# CPUCUIT.net
KiCad netlist of a schematic drawn in Altium Designer
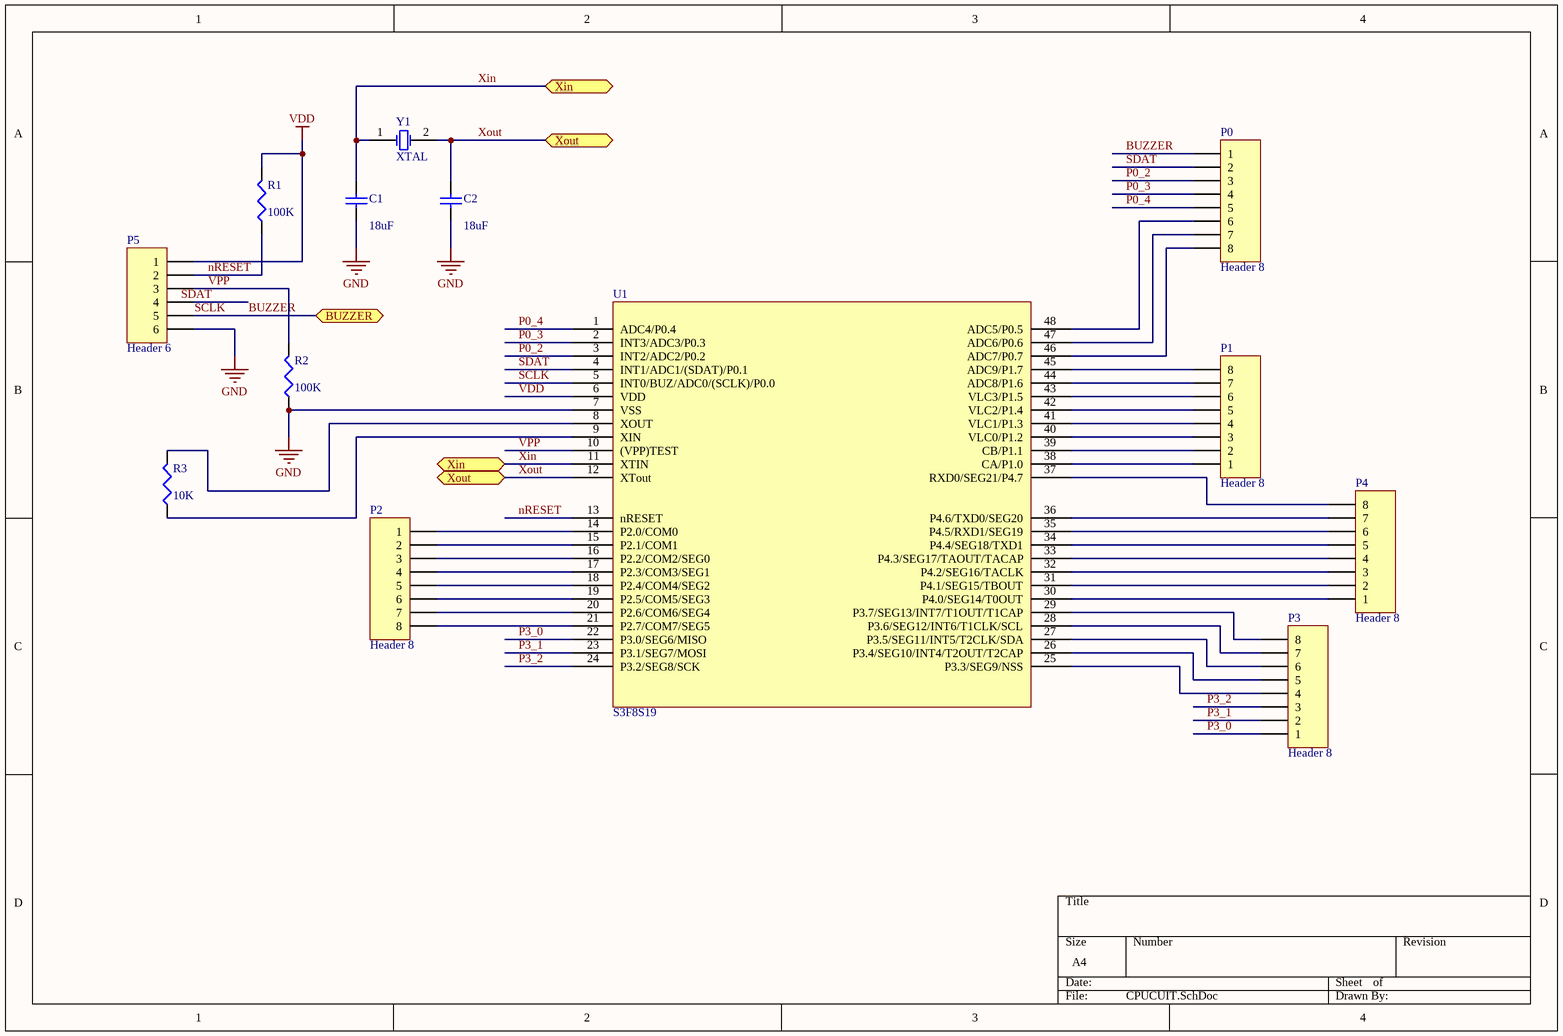
[diagram p0: CPUCUIT.SchDoc]

(export (version "E")
  (design (tool "Eeschema 10.0.6"))
  (components
    (comp (ref "C1")
      (value "18uF")
      (footprint "1608[0603]")
      (description "Capacitor (Semiconductor SIM Model)")
      (fields (field (name "Comment") "Cap Semi") (field (name "PUBLISHER") "Altium Limited"))
      (libsource (lib "Miscellaneous Devices") (part "Cap Semi"))
    )
    (comp (ref "C2")
      (value "18uF")
      (footprint "1608[0603]")
      (description "Capacitor (Semiconductor SIM Model)")
      (fields (field (name "Comment") "Cap Semi") (field (name "PUBLISHER") "Altium Limited"))
      (libsource (lib "Miscellaneous Devices") (part "Cap Semi"))
    )
    (comp (ref "P0")
      (value "Header 8")
      (footprint "HDR1X8")
      (description "Header, 8-Pin")
      (fields (field (name "PUBLISHER") "Altium Limited"))
      (libsource (lib "") (part "Header 8_1"))
    )
    (comp (ref "P1")
      (value "Header 8")
      (footprint "HDR1X8")
      (description "Header, 8-Pin")
      (fields (field (name "PUBLISHER") "Altium Limited"))
      (libsource (lib "Miscellaneous Connectors") (part "Header 8"))
    )
    (comp (ref "P2")
      (value "Header 8")
      (footprint "HDR1X8")
      (description "Header, 8-Pin")
      (fields (field (name "PUBLISHER") "Altium Limited"))
      (libsource (lib "") (part "Header 8_2"))
    )
    (comp (ref "P3")
      (value "Header 8")
      (footprint "HDR1X8")
      (description "Header, 8-Pin")
      (fields (field (name "PUBLISHER") "Altium Limited"))
      (libsource (lib "Miscellaneous Connectors") (part "Header 8"))
    )
    (comp (ref "P4")
      (value "Header 8")
      (footprint "HDR1X8")
      (description "Header, 8-Pin")
      (fields (field (name "PUBLISHER") "Altium Limited"))
      (libsource (lib "Miscellaneous Connectors") (part "Header 8"))
    )
    (comp (ref "P5")
      (value "Header 6")
      (footprint "HDR1X6")
      (description "Header, 6-Pin")
      (fields (field (name "PUBLISHER") "Altium Limited"))
      (libsource (lib "Miscellaneous Connectors") (part "Header 6"))
    )
    (comp (ref "R1")
      (value "100K")
      (footprint "J1-0603")
      (description "Resistor")
      (fields (field (name "Comment") "Res3") (field (name "PUBLISHER") "Altium Limited"))
      (libsource (lib "Miscellaneous Devices") (part "Res3"))
    )
    (comp (ref "R2")
      (value "100K")
      (footprint "J1-0603")
      (description "Resistor")
      (fields (field (name "Comment") "Res3") (field (name "PUBLISHER") "Altium Limited"))
      (libsource (lib "Miscellaneous Devices") (part "Res3"))
    )
    (comp (ref "R3")
      (value "10K")
      (footprint "J1-0603")
      (description "Resistor")
      (fields (field (name "Comment") "Res3") (field (name "PUBLISHER") "Altium Limited"))
      (libsource (lib "Miscellaneous Devices") (part "Res3"))
    )
    (comp (ref "U1")
      (value "S3F8S19")
      (footprint "QFP75P1335X1335X230-48N")
      (libsource (lib "IOTSchlib") (part "S3F8S19"))
    )
    (comp (ref "Y1")
      (value "XTAL")
      (footprint "R38")
      (description "Crystal Oscillator")
      (fields (field (name "PUBLISHER") "Altium Limited"))
      (libsource (lib "Miscellaneous Devices") (part "XTAL"))
    )
  )
  (nets
    (net (code "1") (name "/BUZZER") (class "Default")
      (node (ref "P0") (pin "1") (pinfunction "1_1") (pintype "passive"))
      (node (ref "P5") (pin "5") (pinfunction "5_5") (pintype "passive"))
      (node (ref "U1") (pin "5") (pinfunction "INT0/BUZ/ADC0/(SCLK)/P0.0_5") (pintype "passive"))
    )
    (net (code "2") (name "/P0_2") (class "Default")
      (node (ref "P0") (pin "3") (pinfunction "3_3") (pintype "passive"))
      (node (ref "U1") (pin "3") (pinfunction "INT2/ADC2/P0.2_3") (pintype "passive"))
    )
    (net (code "3") (name "/P0_3") (class "Default")
      (node (ref "P0") (pin "4") (pinfunction "4_4") (pintype "passive"))
      (node (ref "U1") (pin "2") (pinfunction "INT3/ADC3/P0.3_2") (pintype "passive"))
    )
    (net (code "4") (name "/P0_4") (class "Default")
      (node (ref "P0") (pin "5") (pinfunction "5_5") (pintype "passive"))
      (node (ref "U1") (pin "1") (pinfunction "ADC4/P0.4_1") (pintype "passive"))
    )
    (net (code "5") (name "/P3_0") (class "Default")
      (node (ref "P3") (pin "1") (pinfunction "1_1") (pintype "passive"))
      (node (ref "U1") (pin "22") (pinfunction "P3.0/SEG6/MISO_22") (pintype "passive"))
    )
    (net (code "6") (name "/P3_1") (class "Default")
      (node (ref "P3") (pin "2") (pinfunction "2_2") (pintype "passive"))
      (node (ref "U1") (pin "23") (pinfunction "P3.1/SEG7/MOSI_23") (pintype "passive"))
    )
    (net (code "7") (name "/P3_2") (class "Default")
      (node (ref "P3") (pin "3") (pinfunction "3_3") (pintype "passive"))
      (node (ref "U1") (pin "24") (pinfunction "P3.2/SEG8/SCK_24") (pintype "passive"))
    )
    (net (code "8") (name "/SDAT") (class "Default")
      (node (ref "P0") (pin "2") (pinfunction "2_2") (pintype "passive"))
      (node (ref "U1") (pin "4") (pinfunction "INT1/ADC1/(SDAT)/P0.1_4") (pintype "passive"))
    )
    (net (code "9") (name "/VPP") (class "Default")
      (node (ref "P5") (pin "3") (pinfunction "3_3") (pintype "passive"))
      (node (ref "R2") (pin "2") (pinfunction "2_2") (pintype "passive"))
      (node (ref "U1") (pin "10") (pinfunction "(VPP)TEST_10") (pintype "passive"))
    )
    (net (code "10") (name "/Xin") (class "Default")
      (node (ref "C1") (pin "2") (pinfunction "2_2") (pintype "passive"))
      (node (ref "U1") (pin "11") (pinfunction "XTIN_11") (pintype "passive"))
      (node (ref "Y1") (pin "1") (pinfunction "OSC1_1") (pintype "passive"))
    )
    (net (code "11") (name "/Xout") (class "Default")
      (node (ref "C2") (pin "2") (pinfunction "2_2") (pintype "passive"))
      (node (ref "U1") (pin "12") (pinfunction "XTout_12") (pintype "passive"))
      (node (ref "Y1") (pin "2") (pinfunction "OSC2_2") (pintype "passive"))
    )
    (net (code "12") (name "/nRESET") (class "Default")
      (node (ref "P5") (pin "2") (pinfunction "2_2") (pintype "passive"))
      (node (ref "R1") (pin "1") (pinfunction "1_1") (pintype "passive"))
      (node (ref "U1") (pin "13") (pinfunction "nRESET_13") (pintype "passive"))
    )
    (net (code "13") (name "GND") (class "Default")
      (node (ref "C1") (pin "1") (pinfunction "1_1") (pintype "passive"))
      (node (ref "C2") (pin "1") (pinfunction "1_1") (pintype "passive"))
      (node (ref "P5") (pin "6") (pinfunction "6_6") (pintype "passive"))
      (node (ref "R2") (pin "1") (pinfunction "1_1") (pintype "passive"))
      (node (ref "U1") (pin "7") (pinfunction "VSS_7") (pintype "passive"))
    )
    (net (code "14") (name "Net-(U1-ADC5{slash}P0.5)") (class "Default")
      (node (ref "P0") (pin "6") (pinfunction "6_6") (pintype "passive"))
      (node (ref "U1") (pin "48") (pinfunction "ADC5/P0.5_48") (pintype "passive"))
    )
    (net (code "15") (name "Net-(U1-ADC6{slash}P0.6)") (class "Default")
      (node (ref "P0") (pin "7") (pinfunction "7_7") (pintype "passive"))
      (node (ref "U1") (pin "47") (pinfunction "ADC6/P0.6_47") (pintype "passive"))
    )
    (net (code "16") (name "Net-(U1-ADC7{slash}P0.7)") (class "Default")
      (node (ref "P0") (pin "8") (pinfunction "8_8") (pintype "passive"))
      (node (ref "U1") (pin "46") (pinfunction "ADC7/P0.7_46") (pintype "passive"))
    )
    (net (code "17") (name "Net-(U1-ADC8{slash}P1.6)") (class "Default")
      (node (ref "P1") (pin "7") (pinfunction "7_7") (pintype "passive"))
      (node (ref "U1") (pin "44") (pinfunction "ADC8/P1.6_44") (pintype "passive"))
    )
    (net (code "18") (name "Net-(U1-ADC9{slash}P1.7)") (class "Default")
      (node (ref "P1") (pin "8") (pinfunction "8_8") (pintype "passive"))
      (node (ref "U1") (pin "45") (pinfunction "ADC9/P1.7_45") (pintype "passive"))
    )
    (net (code "19") (name "Net-(U1-CA{slash}P1.0)") (class "Default")
      (node (ref "P1") (pin "1") (pinfunction "1_1") (pintype "passive"))
      (node (ref "U1") (pin "38") (pinfunction "CA/P1.0_38") (pintype "passive"))
    )
    (net (code "20") (name "Net-(U1-CB{slash}P1.1)") (class "Default")
      (node (ref "P1") (pin "2") (pinfunction "2_2") (pintype "passive"))
      (node (ref "U1") (pin "39") (pinfunction "CB/P1.1_39") (pintype "passive"))
    )
    (net (code "21") (name "Net-(U1-P2.0{slash}COM0)") (class "Default")
      (node (ref "P2") (pin "1") (pinfunction "1_1") (pintype "passive"))
      (node (ref "U1") (pin "14") (pinfunction "P2.0/COM0_14") (pintype "passive"))
    )
    (net (code "22") (name "Net-(U1-P2.1{slash}COM1)") (class "Default")
      (node (ref "P2") (pin "2") (pinfunction "2_2") (pintype "passive"))
      (node (ref "U1") (pin "15") (pinfunction "P2.1/COM1_15") (pintype "passive"))
    )
    (net (code "23") (name "Net-(U1-P2.2{slash}COM2{slash}SEG0)") (class "Default")
      (node (ref "P2") (pin "3") (pinfunction "3_3") (pintype "passive"))
      (node (ref "U1") (pin "16") (pinfunction "P2.2/COM2/SEG0_16") (pintype "passive"))
    )
    (net (code "24") (name "Net-(U1-P2.3{slash}COM3{slash}SEG1)") (class "Default")
      (node (ref "P2") (pin "4") (pinfunction "4_4") (pintype "passive"))
      (node (ref "U1") (pin "17") (pinfunction "P2.3/COM3/SEG1_17") (pintype "passive"))
    )
    (net (code "25") (name "Net-(U1-P2.4{slash}COM4{slash}SEG2)") (class "Default")
      (node (ref "P2") (pin "5") (pinfunction "5_5") (pintype "passive"))
      (node (ref "U1") (pin "18") (pinfunction "P2.4/COM4/SEG2_18") (pintype "passive"))
    )
    (net (code "26") (name "Net-(U1-P2.5{slash}COM5{slash}SEG3)") (class "Default")
      (node (ref "P2") (pin "6") (pinfunction "6_6") (pintype "passive"))
      (node (ref "U1") (pin "19") (pinfunction "P2.5/COM5/SEG3_19") (pintype "passive"))
    )
    (net (code "27") (name "Net-(U1-P2.6{slash}COM6{slash}SEG4)") (class "Default")
      (node (ref "P2") (pin "7") (pinfunction "7_7") (pintype "passive"))
      (node (ref "U1") (pin "20") (pinfunction "P2.6/COM6/SEG4_20") (pintype "passive"))
    )
    (net (code "28") (name "Net-(U1-P2.7{slash}COM7{slash}SEG5)") (class "Default")
      (node (ref "P2") (pin "8") (pinfunction "8_8") (pintype "passive"))
      (node (ref "U1") (pin "21") (pinfunction "P2.7/COM7/SEG5_21") (pintype "passive"))
    )
    (net (code "29") (name "Net-(U1-P3.3{slash}SEG9{slash}NSS)") (class "Default")
      (node (ref "P3") (pin "4") (pinfunction "4_4") (pintype "passive"))
      (node (ref "U1") (pin "25") (pinfunction "P3.3/SEG9/NSS_25") (pintype "passive"))
    )
    (net (code "30") (name "Net-(U1-P3.4{slash}SEG10{slash}INT4{slash}T2OUT{slash}T2CAP)") (class "Default")
      (node (ref "P3") (pin "5") (pinfunction "5_5") (pintype "passive"))
      (node (ref "U1") (pin "26") (pinfunction "P3.4/SEG10/INT4/T2OUT/T2CAP_26") (pintype "passive"))
    )
    (net (code "31") (name "Net-(U1-P3.5{slash}SEG11{slash}INT5{slash}T2CLK{slash}SDA)") (class "Default")
      (node (ref "P3") (pin "6") (pinfunction "6_6") (pintype "passive"))
      (node (ref "U1") (pin "27") (pinfunction "P3.5/SEG11/INT5/T2CLK/SDA_27") (pintype "passive"))
    )
    (net (code "32") (name "Net-(U1-P3.6{slash}SEG12{slash}INT6{slash}T1CLK{slash}SCL)") (class "Default")
      (node (ref "P3") (pin "7") (pinfunction "7_7") (pintype "passive"))
      (node (ref "U1") (pin "28") (pinfunction "P3.6/SEG12/INT6/T1CLK/SCL_28") (pintype "passive"))
    )
    (net (code "33") (name "Net-(U1-P3.7{slash}SEG13{slash}INT7{slash}T1OUT{slash}T1CAP)") (class "Default")
      (node (ref "P3") (pin "8") (pinfunction "8_8") (pintype "passive"))
      (node (ref "U1") (pin "29") (pinfunction "P3.7/SEG13/INT7/T1OUT/T1CAP_29") (pintype "passive"))
    )
    (net (code "34") (name "Net-(U1-P4.0{slash}SEG14{slash}T0OUT)") (class "Default")
      (node (ref "P4") (pin "1") (pinfunction "1_1") (pintype "passive"))
      (node (ref "U1") (pin "30") (pinfunction "P4.0/SEG14/T0OUT_30") (pintype "passive"))
    )
    (net (code "35") (name "Net-(U1-P4.1{slash}SEG15{slash}TBOUT)") (class "Default")
      (node (ref "P4") (pin "2") (pinfunction "2_2") (pintype "passive"))
      (node (ref "U1") (pin "31") (pinfunction "P4.1/SEG15/TBOUT_31") (pintype "passive"))
    )
    (net (code "36") (name "Net-(U1-P4.2{slash}SEG16{slash}TACLK)") (class "Default")
      (node (ref "P4") (pin "3") (pinfunction "3_3") (pintype "passive"))
      (node (ref "U1") (pin "32") (pinfunction "P4.2/SEG16/TACLK_32") (pintype "passive"))
    )
    (net (code "37") (name "Net-(U1-P4.3{slash}SEG17{slash}TAOUT{slash}TACAP)") (class "Default")
      (node (ref "P4") (pin "4") (pinfunction "4_4") (pintype "passive"))
      (node (ref "U1") (pin "33") (pinfunction "P4.3/SEG17/TAOUT/TACAP_33") (pintype "passive"))
    )
    (net (code "38") (name "Net-(U1-P4.4{slash}SEG18{slash}TXD1)") (class "Default")
      (node (ref "P4") (pin "5") (pinfunction "5_5") (pintype "passive"))
      (node (ref "U1") (pin "34") (pinfunction "P4.4/SEG18/TXD1_34") (pintype "passive"))
    )
    (net (code "39") (name "Net-(U1-P4.5{slash}RXD1{slash}SEG19)") (class "Default")
      (node (ref "P4") (pin "6") (pinfunction "6_6") (pintype "passive"))
      (node (ref "U1") (pin "35") (pinfunction "P4.5/RXD1/SEG19_35") (pintype "passive"))
    )
    (net (code "40") (name "Net-(U1-P4.6{slash}TXD0{slash}SEG20)") (class "Default")
      (node (ref "P4") (pin "7") (pinfunction "7_7") (pintype "passive"))
      (node (ref "U1") (pin "36") (pinfunction "P4.6/TXD0/SEG20_36") (pintype "passive"))
    )
    (net (code "41") (name "Net-(U1-RXD0{slash}SEG21{slash}P4.7)") (class "Default")
      (node (ref "P4") (pin "8") (pinfunction "8_8") (pintype "passive"))
      (node (ref "U1") (pin "37") (pinfunction "RXD0/SEG21/P4.7_37") (pintype "passive"))
    )
    (net (code "42") (name "Net-(U1-VLC0{slash}P1.2)") (class "Default")
      (node (ref "P1") (pin "3") (pinfunction "3_3") (pintype "passive"))
      (node (ref "U1") (pin "40") (pinfunction "VLC0/P1.2_40") (pintype "passive"))
    )
    (net (code "43") (name "Net-(U1-VLC1{slash}P1.3)") (class "Default")
      (node (ref "P1") (pin "4") (pinfunction "4_4") (pintype "passive"))
      (node (ref "U1") (pin "41") (pinfunction "VLC1/P1.3_41") (pintype "passive"))
    )
    (net (code "44") (name "Net-(U1-VLC2{slash}P1.4)") (class "Default")
      (node (ref "P1") (pin "5") (pinfunction "5_5") (pintype "passive"))
      (node (ref "U1") (pin "42") (pinfunction "VLC2/P1.4_42") (pintype "passive"))
    )
    (net (code "45") (name "Net-(U1-VLC3{slash}P1.5)") (class "Default")
      (node (ref "P1") (pin "6") (pinfunction "6_6") (pintype "passive"))
      (node (ref "U1") (pin "43") (pinfunction "VLC3/P1.5_43") (pintype "passive"))
    )
    (net (code "46") (name "Net-(U1-XIN)") (class "Default")
      (node (ref "R3") (pin "1") (pinfunction "1_1") (pintype "passive"))
      (node (ref "U1") (pin "9") (pinfunction "XIN_9") (pintype "passive"))
    )
    (net (code "47") (name "Net-(U1-XOUT)") (class "Default")
      (node (ref "R3") (pin "2") (pinfunction "2_2") (pintype "passive"))
      (node (ref "U1") (pin "8") (pinfunction "XOUT_8") (pintype "passive"))
    )
    (net (code "48") (name "VDD") (class "Default")
      (node (ref "P5") (pin "1") (pinfunction "1_1") (pintype "passive"))
      (node (ref "R1") (pin "2") (pinfunction "2_2") (pintype "passive"))
      (node (ref "U1") (pin "6") (pinfunction "VDD_6") (pintype "passive"))
    )
    (net (code "49") (name "unconnected-(P5-Pad4)") (class "Default")
      (node (ref "P5") (pin "4") (pinfunction "4_4") (pintype "passive"))
    )
  )
)
